# ControllerV3_0_2.net
KiCad netlist of a schematic drawn in Altium Designer
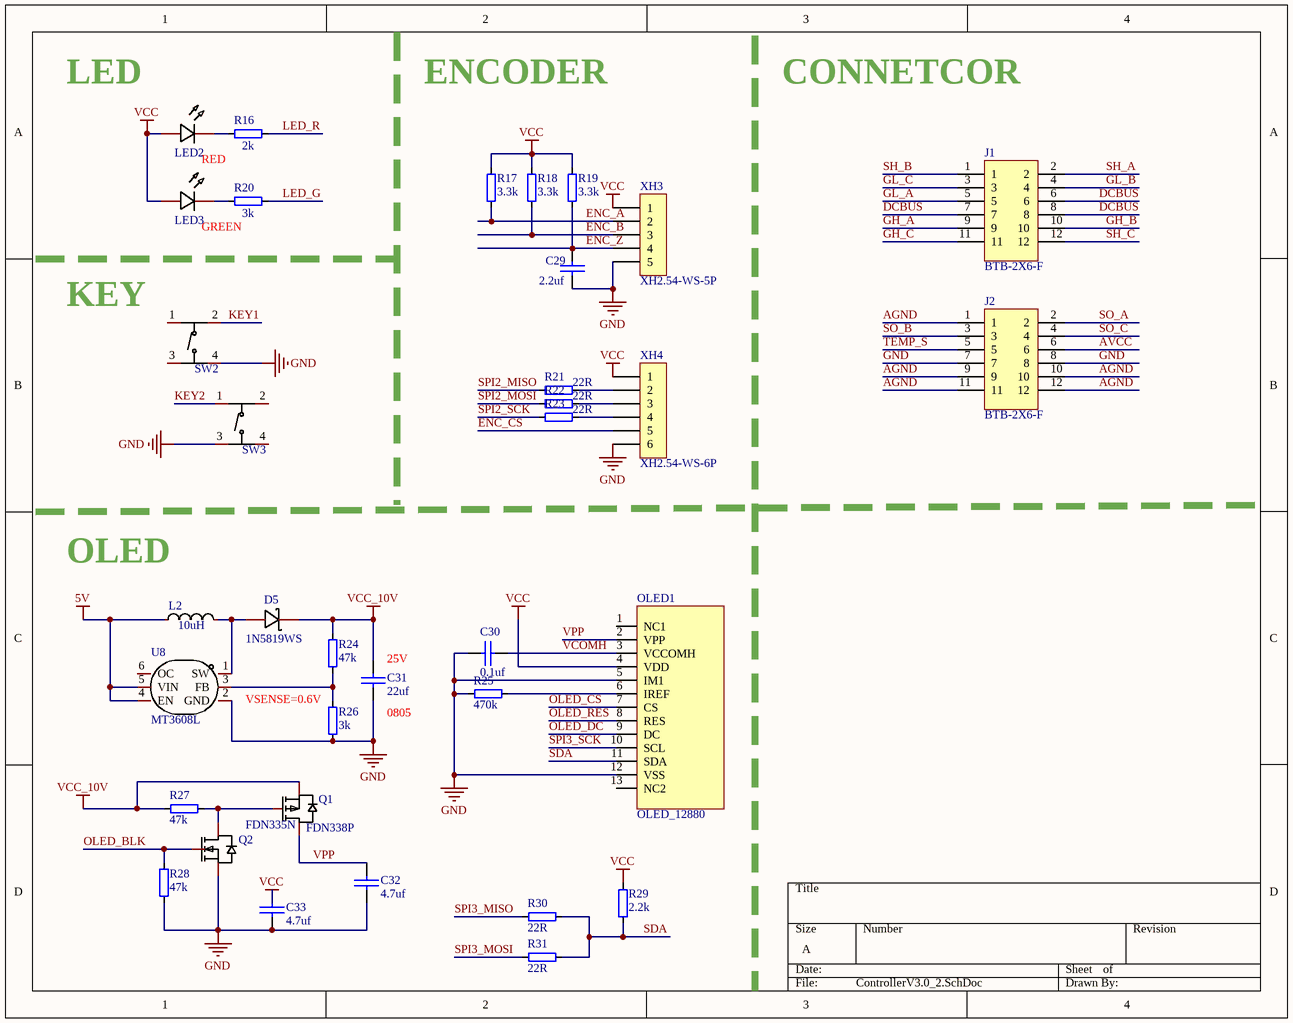
[diagram p0: ControllerV3.0_2.SchDoc]

(export (version "E")
  (design (tool "Eeschema 10.0.6"))
  (components
    (comp (ref "C29")
      (value "2.2uf")
      (footprint "0603C")
      (description "贴片电容")
      (libsource (lib "Controller") (part "CAP"))
    )
    (comp (ref "C30")
      (value "0.1uf")
      (footprint "0603C")
      (description "贴片电容")
      (libsource (lib "Controller") (part "CAP"))
    )
    (comp (ref "C31")
      (value "22uf")
      (footprint "0805C")
      (description "贴片电容")
      (libsource (lib "Controller") (part "CAP"))
    )
    (comp (ref "C32")
      (value "4.7uf")
      (footprint "0603C")
      (description "贴片电容")
      (libsource (lib "Controller") (part "CAP"))
    )
    (comp (ref "C33")
      (value "4.7uf")
      (footprint "0603C")
      (description "贴片电容")
      (libsource (lib "Controller") (part "CAP"))
    )
    (comp (ref "D5")
      (value "1N5819WS")
      (footprint "SOD-323")
      (description "肖特基二极管")
      (fields (field (name "MANUFACTURER") "Hottech(合科泰)"))
      (libsource (lib "Controller") (part "1N5819WS"))
    )
    (comp (ref "J1")
      (value "BTB-2X6-F")
      (footprint "BTB-F-0.8mm-2x6P")
      (description "0.8间距2x6P母座")
      (libsource (lib "Controller") (part "BTB-2X6-F"))
    )
    (comp (ref "J2")
      (value "BTB-2X6-F")
      (footprint "BTB-F-0.8mm-2x6P")
      (description "0.8间距2x6P母座")
      (libsource (lib "Controller") (part "BTB-2X6-F"))
    )
    (comp (ref "L2")
      (value "10uH")
      (footprint "IND-SMD_L3.0-W3.0_SWPA3010S")
      (description "电感值:10uH;精度:±20%;额定电流:920mA;")
      (fields (field (name "MANUFACTURER") "SXN(顺翔诺)") (field (name "MANUFACTURER PART") "SMDRI74-220M"))
      (libsource (lib "Controller") (part "SWPA3015S100MT"))
    )
    (comp (ref "LED2")
      (value "LED_0603-B")
      (footprint "LED_0603")
      (libsource (lib "Controller") (part "LED"))
    )
    (comp (ref "LED3")
      (value "LED_0603-B")
      (footprint "LED_0603")
      (libsource (lib "Controller") (part "LED"))
    )
    (comp (ref "OLED1")
      (value "OLED_12880")
      (footprint "OLED_12880")
      (description "OLED_128*80")
      (libsource (lib "Controller") (part "OLED_12880"))
    )
    (comp (ref "Q1")
      (value "FDN338P")
      (footprint "SOT-23-3")
      (description "P沟道 耐压:20V 电流:2A")
      (fields (field (name "MANUFACTURER") "TECH PUBLIC(台舟)"))
      (libsource (lib "Controller") (part "FDN338P"))
    )
    (comp (ref "Q2")
      (value "FDN335N")
      (footprint "SOT-23-3")
      (description "N沟道 耐压:20V 电流:1.7A")
      (fields (field (name "MANUFACTURER") "TECH PUBLIC(台舟)"))
      (libsource (lib "Controller") (part "FDN335N"))
    )
    (comp (ref "R16")
      (value "2k")
      (footprint "0603R")
      (description "贴片电阻")
      (libsource (lib "Controller") (part "RES"))
    )
    (comp (ref "R17")
      (value "3.3k")
      (footprint "0603R")
      (description "贴片电阻")
      (libsource (lib "Controller") (part "RES"))
    )
    (comp (ref "R18")
      (value "3.3k")
      (footprint "0603R")
      (description "贴片电阻")
      (libsource (lib "Controller") (part "RES"))
    )
    (comp (ref "R19")
      (value "3.3k")
      (footprint "0603R")
      (description "贴片电阻")
      (libsource (lib "Controller") (part "RES"))
    )
    (comp (ref "R20")
      (value "3k")
      (footprint "0603R")
      (description "贴片电阻")
      (libsource (lib "Controller") (part "RES"))
    )
    (comp (ref "R21")
      (value "22R")
      (footprint "0603R")
      (description "贴片电阻")
      (libsource (lib "Controller") (part "RES"))
    )
    (comp (ref "R22")
      (value "22R")
      (footprint "0603R")
      (description "贴片电阻")
      (libsource (lib "Controller") (part "RES"))
    )
    (comp (ref "R23")
      (value "22R")
      (footprint "0603R")
      (description "贴片电阻")
      (libsource (lib "Controller") (part "RES"))
    )
    (comp (ref "R24")
      (value "47k")
      (footprint "0603R")
      (description "贴片电阻")
      (libsource (lib "Controller") (part "RES"))
    )
    (comp (ref "R25")
      (value "470k")
      (footprint "0603R")
      (description "贴片电阻")
      (libsource (lib "Controller") (part "RES"))
    )
    (comp (ref "R26")
      (value "3k")
      (footprint "0603R")
      (description "贴片电阻")
      (libsource (lib "Controller") (part "RES"))
    )
    (comp (ref "R27")
      (value "47k")
      (footprint "0603R")
      (description "贴片电阻")
      (libsource (lib "Controller") (part "RES"))
    )
    (comp (ref "R28")
      (value "47k")
      (footprint "0603R")
      (description "贴片电阻")
      (libsource (lib "Controller") (part "RES"))
    )
    (comp (ref "R29")
      (value "2.2k")
      (footprint "0603R")
      (description "贴片电阻")
      (libsource (lib "Controller") (part "RES"))
    )
    (comp (ref "R30")
      (value "22R")
      (footprint "0603R")
      (description "贴片电阻")
      (libsource (lib "Controller") (part "RES"))
    )
    (comp (ref "R31")
      (value "22R")
      (footprint "0603R")
      (description "贴片电阻")
      (libsource (lib "Controller") (part "RES"))
    )
    (comp (ref "SW2")
      (value "TS-1187A-B-A-B")
      (footprint "TSW SMD-4*4*1.5")
      (description "轻触开关")
      (fields (field (name "MANUFACTURER") "XKB Connectivity(中国星坤)"))
      (libsource (lib "Controller") (part "TS-1187A-B-A-B"))
    )
    (comp (ref "SW3")
      (value "TS-1187A-B-A-B")
      (footprint "TSW SMD-4*4*1.5")
      (description "轻触开关")
      (fields (field (name "MANUFACTURER") "XKB Connectivity(中国星坤)"))
      (libsource (lib "Controller") (part "TS-1187A-B-A-B"))
    )
    (comp (ref "U8")
      (value "MT3608L")
      (footprint "SOT-23-6")
      (fields (field (name "MANUFACTURER") "西安航天民芯"))
      (libsource (lib "Controller") (part "MT3608L"))
    )
    (comp (ref "XH3")
      (value "XH2.54-WS-5P")
      (footprint "XH2.54-WS-5P")
      (libsource (lib "Controller") (part "XH2.54-WS-5P"))
    )
    (comp (ref "XH4")
      (value "XH2.54-WS-6P")
      (footprint "XH2.54-WS-6P")
      (libsource (lib "Controller") (part "XH2.54-WS-6P"))
    )
  )
  (nets
    (net (code "1") (name "/AGND") (class "Default")
      (node (ref "J2") (pin "1") (pinfunction "1_1") (pintype "passive"))
      (node (ref "J2") (pin "10") (pinfunction "10_10") (pintype "passive"))
      (node (ref "J2") (pin "11") (pinfunction "11_11") (pintype "passive"))
      (node (ref "J2") (pin "12") (pinfunction "12_12") (pintype "passive"))
      (node (ref "J2") (pin "9") (pinfunction "9_9") (pintype "passive"))
    )
    (net (code "2") (name "/AVCC") (class "Default")
      (node (ref "J2") (pin "6") (pinfunction "6_6") (pintype "passive"))
    )
    (net (code "3") (name "/DCBUS") (class "Default")
      (node (ref "J1") (pin "6") (pinfunction "6_6") (pintype "passive"))
      (node (ref "J1") (pin "7") (pinfunction "7_7") (pintype "passive"))
      (node (ref "J1") (pin "8") (pinfunction "8_8") (pintype "passive"))
    )
    (net (code "4") (name "/ENC_A") (class "Default")
      (node (ref "R17") (pin "1") (pinfunction "1_1") (pintype "passive"))
      (node (ref "XH3") (pin "2") (pinfunction "2_2") (pintype "passive"))
    )
    (net (code "5") (name "/ENC_B") (class "Default")
      (node (ref "R18") (pin "1") (pinfunction "1_1") (pintype "passive"))
      (node (ref "XH3") (pin "3") (pinfunction "3_3") (pintype "passive"))
    )
    (net (code "6") (name "/ENC_CS") (class "Default")
      (node (ref "XH4") (pin "5") (pinfunction "5_5") (pintype "passive"))
    )
    (net (code "7") (name "/ENC_Z") (class "Default")
      (node (ref "C29") (pin "1") (pinfunction "1_1") (pintype "passive"))
      (node (ref "R19") (pin "1") (pinfunction "1_1") (pintype "passive"))
      (node (ref "XH3") (pin "4") (pinfunction "4_4") (pintype "passive"))
    )
    (net (code "8") (name "/GH_A") (class "Default")
      (node (ref "J1") (pin "9") (pinfunction "9_9") (pintype "passive"))
    )
    (net (code "9") (name "/GH_B") (class "Default")
      (node (ref "J1") (pin "10") (pinfunction "10_10") (pintype "passive"))
    )
    (net (code "10") (name "/GH_C") (class "Default")
      (node (ref "J1") (pin "11") (pinfunction "11_11") (pintype "passive"))
    )
    (net (code "11") (name "/GL_A") (class "Default")
      (node (ref "J1") (pin "5") (pinfunction "5_5") (pintype "passive"))
    )
    (net (code "12") (name "/GL_B") (class "Default")
      (node (ref "J1") (pin "4") (pinfunction "4_4") (pintype "passive"))
    )
    (net (code "13") (name "/GL_C") (class "Default")
      (node (ref "J1") (pin "3") (pinfunction "3_3") (pintype "passive"))
    )
    (net (code "14") (name "/KEY1") (class "Default")
      (node (ref "SW2") (pin "2") (pinfunction "B_2") (pintype "passive"))
    )
    (net (code "15") (name "/KEY2") (class "Default")
      (node (ref "SW3") (pin "1") (pinfunction "A_1") (pintype "passive"))
    )
    (net (code "16") (name "/LED_G") (class "Default")
      (node (ref "R20") (pin "2") (pinfunction "2_2") (pintype "passive"))
    )
    (net (code "17") (name "/LED_R") (class "Default")
      (node (ref "R16") (pin "2") (pinfunction "2_2") (pintype "passive"))
    )
    (net (code "18") (name "/OLED_BLK") (class "Default")
      (node (ref "Q2") (pin "1") (pinfunction "G_1") (pintype "passive"))
      (node (ref "R28") (pin "2") (pinfunction "2_2") (pintype "passive"))
    )
    (net (code "19") (name "/OLED_CS") (class "Default")
      (node (ref "OLED1") (pin "7") (pinfunction "CS_7") (pintype "passive"))
    )
    (net (code "20") (name "/OLED_DC") (class "Default")
      (node (ref "OLED1") (pin "9") (pinfunction "DC_9") (pintype "passive"))
    )
    (net (code "21") (name "/OLED_RES") (class "Default")
      (node (ref "OLED1") (pin "8") (pinfunction "RES_8") (pintype "passive"))
    )
    (net (code "22") (name "/SDA") (class "Default")
      (node (ref "OLED1") (pin "11") (pinfunction "SDA_11") (pintype "passive"))
      (node (ref "R29") (pin "1") (pinfunction "1_1") (pintype "passive"))
      (node (ref "R30") (pin "2") (pinfunction "2_2") (pintype "passive"))
      (node (ref "R31") (pin "2") (pinfunction "2_2") (pintype "passive"))
    )
    (net (code "23") (name "/SH_A") (class "Default")
      (node (ref "J1") (pin "2") (pinfunction "2_2") (pintype "passive"))
    )
    (net (code "24") (name "/SH_B") (class "Default")
      (node (ref "J1") (pin "1") (pinfunction "1_1") (pintype "passive"))
    )
    (net (code "25") (name "/SH_C") (class "Default")
      (node (ref "J1") (pin "12") (pinfunction "12_12") (pintype "passive"))
    )
    (net (code "26") (name "/SO_A") (class "Default")
      (node (ref "J2") (pin "2") (pinfunction "2_2") (pintype "passive"))
    )
    (net (code "27") (name "/SO_B") (class "Default")
      (node (ref "J2") (pin "3") (pinfunction "3_3") (pintype "passive"))
    )
    (net (code "28") (name "/SO_C") (class "Default")
      (node (ref "J2") (pin "4") (pinfunction "4_4") (pintype "passive"))
    )
    (net (code "29") (name "/SPI2_MISO") (class "Default")
      (node (ref "R21") (pin "1") (pinfunction "1_1") (pintype "passive"))
    )
    (net (code "30") (name "/SPI2_MOSI") (class "Default")
      (node (ref "R22") (pin "1") (pinfunction "1_1") (pintype "passive"))
    )
    (net (code "31") (name "/SPI2_SCK") (class "Default")
      (node (ref "R23") (pin "1") (pinfunction "1_1") (pintype "passive"))
    )
    (net (code "32") (name "/SPI3_MISO") (class "Default")
      (node (ref "R30") (pin "1") (pinfunction "1_1") (pintype "passive"))
    )
    (net (code "33") (name "/SPI3_MOSI") (class "Default")
      (node (ref "R31") (pin "1") (pinfunction "1_1") (pintype "passive"))
    )
    (net (code "34") (name "/SPI3_SCK") (class "Default")
      (node (ref "OLED1") (pin "10") (pinfunction "SCL_10") (pintype "passive"))
    )
    (net (code "35") (name "/TEMP_S") (class "Default")
      (node (ref "J2") (pin "5") (pinfunction "5_5") (pintype "passive"))
    )
    (net (code "36") (name "/VCOMH") (class "Default")
      (node (ref "C30") (pin "2") (pinfunction "2_2") (pintype "passive"))
      (node (ref "OLED1") (pin "3") (pinfunction "VCCOMH_3") (pintype "passive"))
    )
    (net (code "37") (name "/VPP") (class "Default")
      (node (ref "C32") (pin "1") (pinfunction "1_1") (pintype "passive"))
      (node (ref "OLED1") (pin "2") (pinfunction "VPP_2") (pintype "passive"))
      (node (ref "Q1") (pin "3") (pinfunction "D_3") (pintype "passive"))
    )
    (net (code "38") (name "5V") (class "Default")
      (node (ref "L2") (pin "1") (pinfunction "1_1") (pintype "passive"))
      (node (ref "U8") (pin "4") (pinfunction "EN_4") (pintype "passive"))
      (node (ref "U8") (pin "5") (pinfunction "VIN_5") (pintype "passive"))
    )
    (net (code "39") (name "GND") (class "Default")
      (node (ref "C29") (pin "2") (pinfunction "2_2") (pintype "passive"))
      (node (ref "C30") (pin "1") (pinfunction "1_1") (pintype "passive"))
      (node (ref "C31") (pin "2") (pinfunction "2_2") (pintype "passive"))
      (node (ref "C32") (pin "2") (pinfunction "2_2") (pintype "passive"))
      (node (ref "C33") (pin "2") (pinfunction "2_2") (pintype "passive"))
      (node (ref "J2") (pin "7") (pinfunction "7_7") (pintype "passive"))
      (node (ref "J2") (pin "8") (pinfunction "8_8") (pintype "passive"))
      (node (ref "OLED1") (pin "12") (pinfunction "VSS_12") (pintype "passive"))
      (node (ref "OLED1") (pin "5") (pinfunction "IM1_5") (pintype "passive"))
      (node (ref "Q2") (pin "2") (pinfunction "S_2") (pintype "passive"))
      (node (ref "R25") (pin "1") (pinfunction "1_1") (pintype "passive"))
      (node (ref "R26") (pin "1") (pinfunction "1_1") (pintype "passive"))
      (node (ref "R28") (pin "1") (pinfunction "1_1") (pintype "passive"))
      (node (ref "SW2") (pin "4") (pinfunction "D_4") (pintype "passive"))
      (node (ref "SW3") (pin "3") (pinfunction "C_3") (pintype "passive"))
      (node (ref "U8") (pin "2") (pinfunction "GND_2") (pintype "passive"))
      (node (ref "XH3") (pin "5") (pinfunction "5_5") (pintype "passive"))
      (node (ref "XH4") (pin "6") (pinfunction "6_6") (pintype "passive"))
    )
    (net (code "40") (name "Net-(D5-A)") (class "Default")
      (node (ref "D5") (pin "2") (pinfunction "A_2") (pintype "passive"))
      (node (ref "L2") (pin "2") (pinfunction "2_2") (pintype "passive"))
      (node (ref "U8") (pin "1") (pinfunction "SW_1") (pintype "passive"))
    )
    (net (code "41") (name "Net-(LED2-C)") (class "Default")
      (node (ref "LED2") (pin "1") (pinfunction "C_1") (pintype "passive"))
      (node (ref "R16") (pin "1") (pinfunction "1_1") (pintype "passive"))
    )
    (net (code "42") (name "Net-(LED3-C)") (class "Default")
      (node (ref "LED3") (pin "1") (pinfunction "C_1") (pintype "passive"))
      (node (ref "R20") (pin "1") (pinfunction "1_1") (pintype "passive"))
    )
    (net (code "43") (name "Net-(OLED1-IREF)") (class "Default")
      (node (ref "OLED1") (pin "6") (pinfunction "IREF_6") (pintype "passive"))
      (node (ref "R25") (pin "2") (pinfunction "2_2") (pintype "passive"))
    )
    (net (code "44") (name "Net-(Q1-G)") (class "Default")
      (node (ref "Q1") (pin "1") (pinfunction "G_1") (pintype "passive"))
      (node (ref "Q2") (pin "3") (pinfunction "D_3") (pintype "passive"))
      (node (ref "R27") (pin "2") (pinfunction "2_2") (pintype "passive"))
    )
    (net (code "45") (name "Net-(R21-Pad2)") (class "Default")
      (node (ref "R21") (pin "2") (pinfunction "2_2") (pintype "passive"))
      (node (ref "XH4") (pin "2") (pinfunction "2_2") (pintype "passive"))
    )
    (net (code "46") (name "Net-(R22-Pad2)") (class "Default")
      (node (ref "R22") (pin "2") (pinfunction "2_2") (pintype "passive"))
      (node (ref "XH4") (pin "3") (pinfunction "3_3") (pintype "passive"))
    )
    (net (code "47") (name "Net-(R23-Pad2)") (class "Default")
      (node (ref "R23") (pin "2") (pinfunction "2_2") (pintype "passive"))
      (node (ref "XH4") (pin "4") (pinfunction "4_4") (pintype "passive"))
    )
    (net (code "48") (name "Net-(U8-FB)") (class "Default")
      (node (ref "R24") (pin "1") (pinfunction "1_1") (pintype "passive"))
      (node (ref "R26") (pin "2") (pinfunction "2_2") (pintype "passive"))
      (node (ref "U8") (pin "3") (pinfunction "FB_3") (pintype "passive"))
    )
    (net (code "49") (name "VCC") (class "Default")
      (node (ref "C33") (pin "1") (pinfunction "1_1") (pintype "passive"))
      (node (ref "LED2") (pin "2") (pinfunction "A_2") (pintype "passive"))
      (node (ref "LED3") (pin "2") (pinfunction "A_2") (pintype "passive"))
      (node (ref "OLED1") (pin "4") (pinfunction "VDD_4") (pintype "passive"))
      (node (ref "R17") (pin "2") (pinfunction "2_2") (pintype "passive"))
      (node (ref "R18") (pin "2") (pinfunction "2_2") (pintype "passive"))
      (node (ref "R19") (pin "2") (pinfunction "2_2") (pintype "passive"))
      (node (ref "R29") (pin "2") (pinfunction "2_2") (pintype "passive"))
      (node (ref "XH3") (pin "1") (pinfunction "1_1") (pintype "passive"))
      (node (ref "XH4") (pin "1") (pinfunction "1_1") (pintype "passive"))
    )
    (net (code "50") (name "VCC_10V") (class "Default")
      (node (ref "C31") (pin "1") (pinfunction "1_1") (pintype "passive"))
      (node (ref "D5") (pin "1") (pinfunction "K_1") (pintype "passive"))
      (node (ref "Q1") (pin "2") (pinfunction "S_2") (pintype "passive"))
      (node (ref "R24") (pin "2") (pinfunction "2_2") (pintype "passive"))
      (node (ref "R27") (pin "1") (pinfunction "1_1") (pintype "passive"))
    )
    (net (code "51") (name "unconnected-(OLED1-NC1-Pad1)") (class "Default")
      (node (ref "OLED1") (pin "1") (pinfunction "NC1_1") (pintype "passive"))
    )
    (net (code "52") (name "unconnected-(OLED1-NC2-Pad13)") (class "Default")
      (node (ref "OLED1") (pin "13") (pinfunction "NC2_13") (pintype "passive"))
    )
    (net (code "53") (name "unconnected-(SW2-A-Pad1)") (class "Default")
      (node (ref "SW2") (pin "1") (pinfunction "A_1") (pintype "passive"))
    )
    (net (code "54") (name "unconnected-(SW2-C-Pad3)") (class "Default")
      (node (ref "SW2") (pin "3") (pinfunction "C_3") (pintype "passive"))
    )
    (net (code "55") (name "unconnected-(SW3-B-Pad2)") (class "Default")
      (node (ref "SW3") (pin "2") (pinfunction "B_2") (pintype "passive"))
    )
    (net (code "56") (name "unconnected-(SW3-D-Pad4)") (class "Default")
      (node (ref "SW3") (pin "4") (pinfunction "D_4") (pintype "passive"))
    )
    (net (code "57") (name "unconnected-(U8-OC-Pad6)") (class "Default")
      (node (ref "U8") (pin "6") (pinfunction "OC_6") (pintype "passive"))
    )
  )
)
